# V1_4.net
KiCad netlist of a schematic drawn in Altium Designer
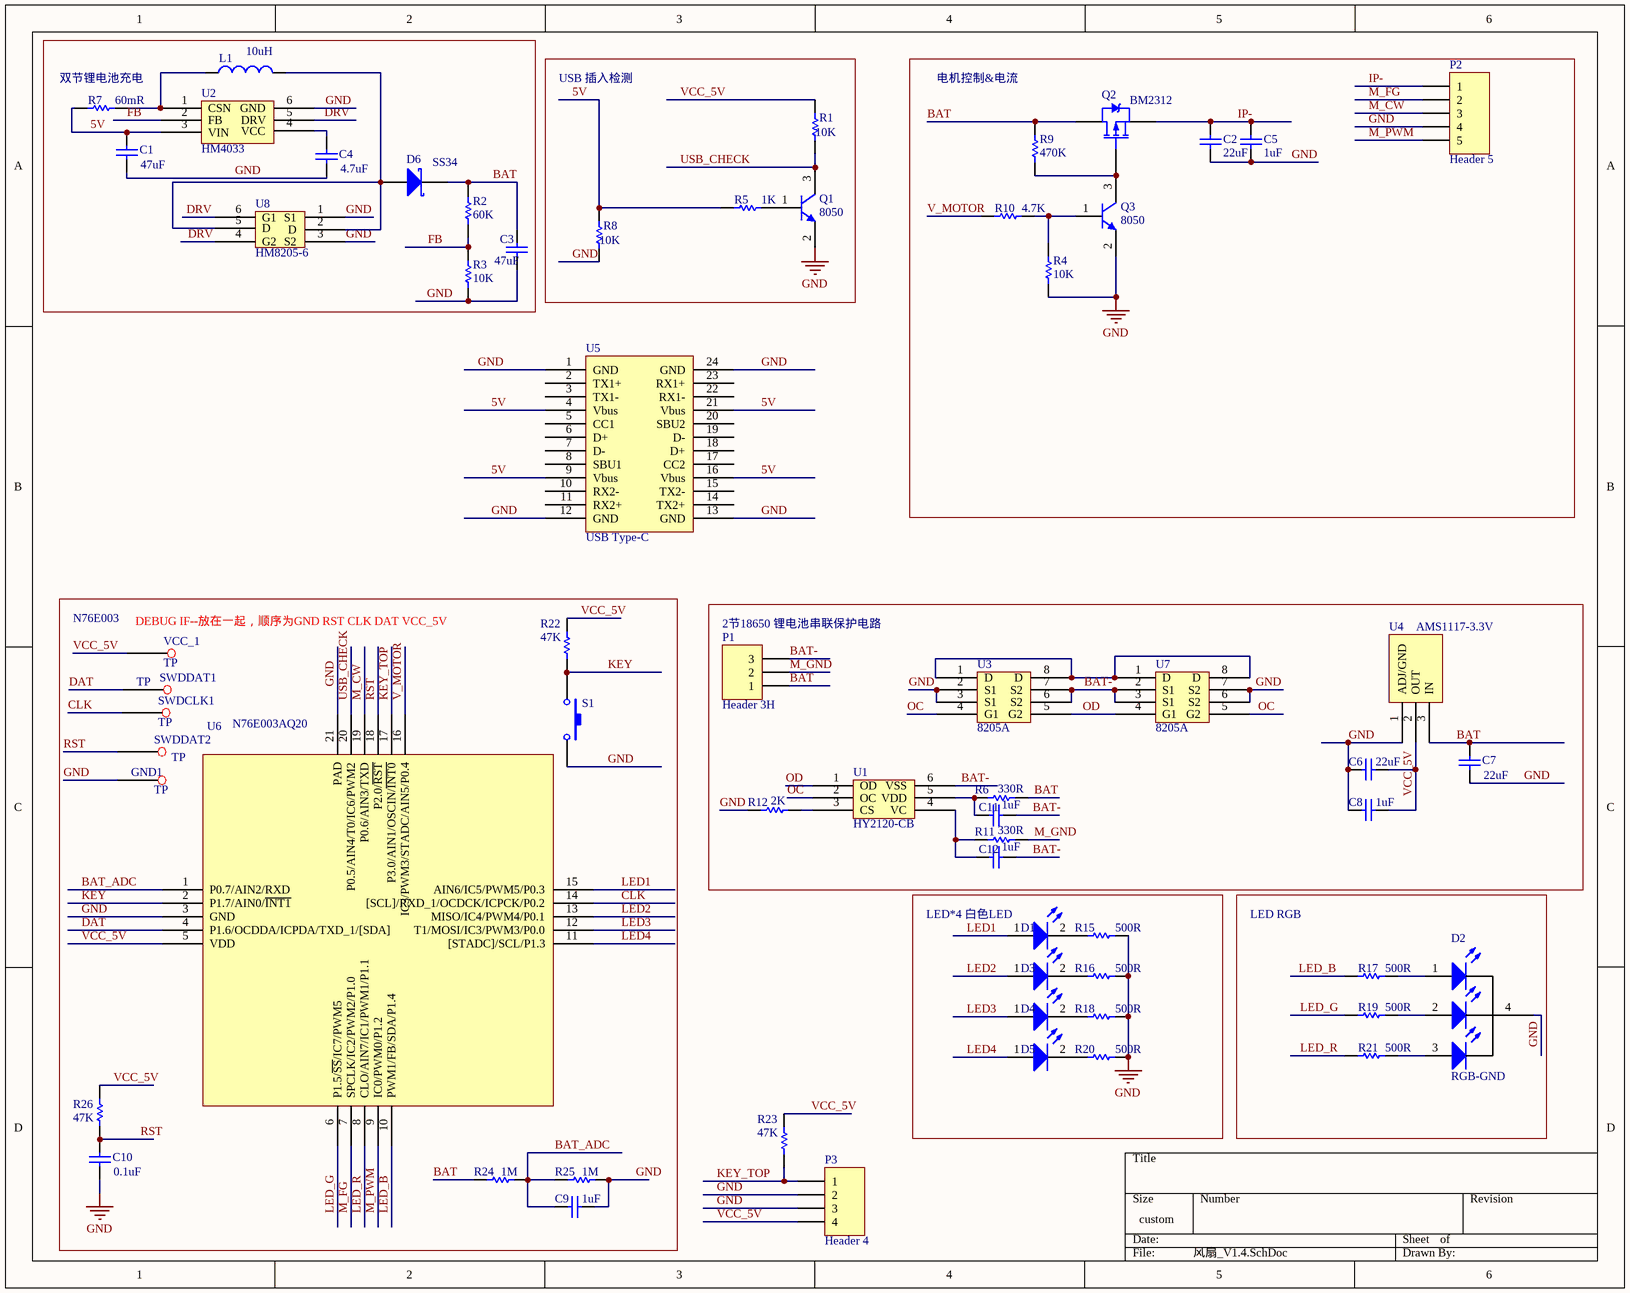
[diagram p0: 风扇_V1.4.SchDoc]

(export (version "E")
  (design (tool "Eeschema 10.0.6"))
  (components
    (comp (ref "C1")
      (value "47uF")
      (footprint "C-0603")
      (description "Capacitor")
      (fields (field (name "PUBLISHER") "Altium Limited"))
      (libsource (lib "Miscellaneous Devices") (part "Cap"))
    )
    (comp (ref "C2")
      (value "22uF")
      (footprint "C-0603")
      (description "Capacitor")
      (fields (field (name "PUBLISHER") "Altium Limited"))
      (libsource (lib "Miscellaneous Devices") (part "Cap"))
    )
    (comp (ref "C3")
      (value "47uF")
      (footprint "C-0603")
      (description "Capacitor")
      (fields (field (name "PUBLISHER") "Altium Limited"))
      (libsource (lib "Miscellaneous Devices") (part "Cap"))
    )
    (comp (ref "C4")
      (value "4.7uF")
      (footprint "C-0402")
      (description "Capacitor")
      (fields (field (name "PUBLISHER") "Altium Limited"))
      (libsource (lib "Miscellaneous Devices") (part "Cap"))
    )
    (comp (ref "C5")
      (value "1uF")
      (footprint "C-0402")
      (description "Capacitor")
      (fields (field (name "PUBLISHER") "Altium Limited"))
      (libsource (lib "Miscellaneous Devices") (part "Cap"))
    )
    (comp (ref "C6")
      (value "22uF")
      (footprint "C-0603")
      (description "Capacitor")
      (fields (field (name "PUBLISHER") "Altium Limited"))
      (libsource (lib "Miscellaneous Devices") (part "Cap"))
    )
    (comp (ref "C7")
      (value "22uF")
      (footprint "C-0603")
      (description "Capacitor")
      (fields (field (name "PUBLISHER") "Altium Limited"))
      (libsource (lib "Miscellaneous Devices") (part "Cap"))
    )
    (comp (ref "C8")
      (value "1uF")
      (footprint "C-0402")
      (description "Capacitor")
      (fields (field (name "PUBLISHER") "Altium Limited"))
      (libsource (lib "Miscellaneous Devices") (part "Cap"))
    )
    (comp (ref "C9")
      (value "1uF")
      (footprint "C-0402")
      (description "Capacitor")
      (fields (field (name "PUBLISHER") "Altium Limited"))
      (libsource (lib "Miscellaneous Devices") (part "Cap"))
    )
    (comp (ref "C10")
      (value "0.1uF")
      (footprint "C-0402")
      (description "Capacitor")
      (fields (field (name "PUBLISHER") "Altium Limited"))
      (libsource (lib "Miscellaneous Devices") (part "Cap"))
    )
    (comp (ref "C11")
      (value "1uF")
      (footprint "C-0402")
      (description "Capacitor")
      (fields (field (name "PUBLISHER") "Altium Limited"))
      (libsource (lib "Miscellaneous Devices") (part "Cap"))
    )
    (comp (ref "C12")
      (value "1uF")
      (footprint "C-0402")
      (description "Capacitor")
      (fields (field (name "PUBLISHER") "Altium Limited"))
      (libsource (lib "Miscellaneous Devices") (part "Cap"))
    )
    (comp (ref "D1")
      (value "LED0")
      (footprint "LED-0603")
      (description "Typical INFRARED GaAs LED")
      (fields (field (name "PUBLISHER") "Altium Limited"))
      (libsource (lib "Miscellaneous Devices") (part "LED0"))
    )
    (comp (ref "D2")
      (value "RGB-GND")
      (footprint "0603*2-LED")
      (libsource (lib "Others_IC_SCH_LIB") (part "RGB-GND"))
    )
    (comp (ref "D3")
      (value "LED0")
      (footprint "LED-0603")
      (description "Typical INFRARED GaAs LED")
      (fields (field (name "PUBLISHER") "Altium Limited"))
      (libsource (lib "Miscellaneous Devices") (part "LED0"))
    )
    (comp (ref "D4")
      (value "LED0")
      (footprint "LED-0603")
      (description "Typical INFRARED GaAs LED")
      (fields (field (name "PUBLISHER") "Altium Limited"))
      (libsource (lib "Miscellaneous Devices") (part "LED0"))
    )
    (comp (ref "D5")
      (value "LED0")
      (footprint "LED-0603")
      (description "Typical INFRARED GaAs LED")
      (fields (field (name "PUBLISHER") "Altium Limited"))
      (libsource (lib "Miscellaneous Devices") (part "LED0"))
    )
    (comp (ref "D6")
      (value "SS34")
      (footprint "HM4033 V1.0:DSMD")
      (description "Schottky Rectifier")
      (fields (field (name "PUBLISHER") "Altium Limited"))
      (libsource (lib "Miscellaneous Devices") (part "Diode 10TQ035"))
    )
    (comp (ref "GND1") (value "TP") (footprint "TP-1.5") (libsource (lib "Others_IC_SCH_LIB") (part "TP")))
    (comp (ref "L1")
      (value "10uH")
      (footprint "L-SMD")
      (description "Inductor")
      (fields (field (name "PUBLISHER") "Altium Limited"))
      (libsource (lib "Miscellaneous Devices") (part "Inductor"))
    )
    (comp (ref "P1")
      (value "Header 3H")
      (footprint "HED1X3")
      (description "Header, 3-Pin, Right Angle")
      (fields (field (name "PUBLISHER") "Altium Limited"))
      (libsource (lib "Miscellaneous Connectors") (part "Header 3H"))
    )
    (comp (ref "P2")
      (value "Header 5")
      (footprint "HDR1X5")
      (description "Header, 5-Pin")
      (fields (field (name "PUBLISHER") "Altium Limited"))
      (libsource (lib "Miscellaneous Connectors") (part "Header 5"))
    )
    (comp (ref "P3")
      (value "Header 4")
      (footprint "HDR1X4")
      (description "Header, 4-Pin")
      (fields (field (name "PUBLISHER") "Altium Limited"))
      (libsource (lib "Miscellaneous Connectors") (part "Header 4"))
    )
    (comp (ref "Q1")
      (value "8050")
      (footprint "SOT-23")
      (description "NPN Bipolar Transistor")
      (fields (field (name "PUBLISHER") "Altium Limited"))
      (libsource (lib "Miscellaneous Devices") (part "NPN"))
    )
    (comp (ref "Q2")
      (value "BM2312")
      (footprint "SOT-23")
      (description "P-Channel Power MOSFET")
      (fields (field (name "PUBLISHER") "Altium Limited"))
      (libsource (lib "Miscellaneous Devices") (part "PMOS-2"))
    )
    (comp (ref "Q3")
      (value "8050")
      (footprint "SOT-23")
      (description "NPN Bipolar Transistor")
      (fields (field (name "PUBLISHER") "Altium Limited"))
      (libsource (lib "Miscellaneous Devices") (part "NPN"))
    )
    (comp (ref "R1")
      (value "10K")
      (footprint "R-0402")
      (description "Resistor")
      (fields (field (name "PUBLISHER") "Altium Limited"))
      (libsource (lib "Miscellaneous Devices") (part "Res1"))
    )
    (comp (ref "R2")
      (value "60K")
      (footprint "R-0402")
      (description "Resistor")
      (fields (field (name "PUBLISHER") "Altium Limited"))
      (libsource (lib "Miscellaneous Devices") (part "Res1"))
    )
    (comp (ref "R3")
      (value "10K")
      (footprint "R-0402")
      (description "Resistor")
      (fields (field (name "PUBLISHER") "Altium Limited"))
      (libsource (lib "Miscellaneous Devices") (part "Res1"))
    )
    (comp (ref "R4")
      (value "10K")
      (footprint "R-0402")
      (description "Resistor")
      (fields (field (name "PUBLISHER") "Altium Limited"))
      (libsource (lib "Miscellaneous Devices") (part "Res1"))
    )
    (comp (ref "R5")
      (value "1K")
      (footprint "R-0402")
      (description "Resistor")
      (fields (field (name "PUBLISHER") "Altium Limited"))
      (libsource (lib "Miscellaneous Devices") (part "Res1"))
    )
    (comp (ref "R6")
      (value "330R")
      (footprint "R-0402")
      (description "Resistor")
      (fields (field (name "PUBLISHER") "Altium Limited"))
      (libsource (lib "Miscellaneous Devices") (part "Res1"))
    )
    (comp (ref "R7")
      (value "60mR")
      (footprint "R-0402")
      (description "Resistor")
      (fields (field (name "PUBLISHER") "Altium Limited"))
      (libsource (lib "Miscellaneous Devices") (part "Res1"))
    )
    (comp (ref "R8")
      (value "10K")
      (footprint "R-0402")
      (description "Resistor")
      (fields (field (name "PUBLISHER") "Altium Limited"))
      (libsource (lib "Miscellaneous Devices") (part "Res1"))
    )
    (comp (ref "R9")
      (value "470K")
      (footprint "R-0402")
      (description "Resistor")
      (fields (field (name "PUBLISHER") "Altium Limited"))
      (libsource (lib "Miscellaneous Devices") (part "Res1"))
    )
    (comp (ref "R10")
      (value "4.7K")
      (footprint "R-0402")
      (description "Resistor")
      (fields (field (name "PUBLISHER") "Altium Limited"))
      (libsource (lib "Miscellaneous Devices") (part "Res1"))
    )
    (comp (ref "R11")
      (value "330R")
      (footprint "R-0402")
      (description "Resistor")
      (fields (field (name "PUBLISHER") "Altium Limited"))
      (libsource (lib "Miscellaneous Devices") (part "Res1"))
    )
    (comp (ref "R12")
      (value "2K")
      (footprint "R-0402")
      (description "Resistor")
      (fields (field (name "PUBLISHER") "Altium Limited"))
      (libsource (lib "Miscellaneous Devices") (part "Res1"))
    )
    (comp (ref "R15")
      (value "500R")
      (footprint "R-0402")
      (description "Resistor")
      (fields (field (name "PUBLISHER") "Altium Limited"))
      (libsource (lib "Miscellaneous Devices") (part "Res1"))
    )
    (comp (ref "R16")
      (value "500R")
      (footprint "R-0402")
      (description "Resistor")
      (fields (field (name "PUBLISHER") "Altium Limited"))
      (libsource (lib "Miscellaneous Devices") (part "Res1"))
    )
    (comp (ref "R17")
      (value "500R")
      (footprint "R-0402")
      (description "Resistor")
      (fields (field (name "PUBLISHER") "Altium Limited"))
      (libsource (lib "Miscellaneous Devices") (part "Res1"))
    )
    (comp (ref "R18")
      (value "500R")
      (footprint "R-0402")
      (description "Resistor")
      (fields (field (name "PUBLISHER") "Altium Limited"))
      (libsource (lib "Miscellaneous Devices") (part "Res1"))
    )
    (comp (ref "R19")
      (value "500R")
      (footprint "R-0402")
      (description "Resistor")
      (fields (field (name "PUBLISHER") "Altium Limited"))
      (libsource (lib "Miscellaneous Devices") (part "Res1"))
    )
    (comp (ref "R20")
      (value "500R")
      (footprint "R-0402")
      (description "Resistor")
      (fields (field (name "PUBLISHER") "Altium Limited"))
      (libsource (lib "Miscellaneous Devices") (part "Res1"))
    )
    (comp (ref "R21")
      (value "500R")
      (footprint "R-0402")
      (description "Resistor")
      (fields (field (name "PUBLISHER") "Altium Limited"))
      (libsource (lib "Miscellaneous Devices") (part "Res1"))
    )
    (comp (ref "R22")
      (value "47K")
      (footprint "R-0402")
      (description "Resistor")
      (fields (field (name "PUBLISHER") "Altium Limited"))
      (libsource (lib "Miscellaneous Devices") (part "Res1"))
    )
    (comp (ref "R23")
      (value "47K")
      (footprint "R-0402")
      (description "Resistor")
      (fields (field (name "PUBLISHER") "Altium Limited"))
      (libsource (lib "Miscellaneous Devices") (part "Res1"))
    )
    (comp (ref "R24")
      (value "1M")
      (footprint "R-0402")
      (description "Resistor")
      (fields (field (name "PUBLISHER") "Altium Limited"))
      (libsource (lib "Miscellaneous Devices") (part "Res1"))
    )
    (comp (ref "R25")
      (value "1M")
      (footprint "R-0402")
      (description "Resistor")
      (fields (field (name "PUBLISHER") "Altium Limited"))
      (libsource (lib "Miscellaneous Devices") (part "Res1"))
    )
    (comp (ref "R26")
      (value "47K")
      (footprint "R-0402")
      (description "Resistor")
      (fields (field (name "PUBLISHER") "Altium Limited"))
      (libsource (lib "Miscellaneous Devices") (part "Res1"))
    )
    (comp (ref "S1")
      (value "SW-PB")
      (footprint "SW-6*6*4.3")
      (description "Switch")
      (fields (field (name "PUBLISHER") "Altium Limited"))
      (libsource (lib "Miscellaneous Devices") (part "SW-PB"))
    )
    (comp (ref "SWDCLK1") (value "TP") (footprint "TP-1.5") (libsource (lib "Others_IC_SCH_LIB") (part "TP")))
    (comp (ref "SWDDAT1") (value "TP") (footprint "TP-1.5") (libsource (lib "Others_IC_SCH_LIB") (part "TP")))
    (comp (ref "SWDDAT2") (value "TP") (footprint "TP-1.5") (libsource (lib "Others_IC_SCH_LIB") (part "TP")))
    (comp (ref "U1")
      (value "HY2120-CB")
      (footprint "SOT-23-6L")
      (libsource (lib "Others_IC_SCH_LIB") (part "HY2120"))
    )
    (comp (ref "U2")
      (value "HM4033")
      (footprint "SOT-23-6L")
      (libsource (lib "Others_IC_SCH_LIB") (part "HM4033"))
    )
    (comp (ref "U3")
      (value "8205A")
      (footprint "TSSOP8")
      (libsource (lib "Others_IC_SCH_LIB") (part "8205A"))
    )
    (comp (ref "U4")
      (value "AMS1117-3.3V")
      (footprint "SOT-223")
      (libsource (lib "Others_IC_SCH_LIB") (part "AMS1117"))
    )
    (comp (ref "U5")
      (value "USB Type-C")
      (footprint "USB-type C")
      (libsource (lib "Others_IC_SCH_LIB") (part "USB Type-C"))
    )
    (comp (ref "U6")
      (value "N76E003AQ20")
      (footprint "QFN-20 0.4mm")
      (libsource (lib "Others_IC_SCH_LIB") (part "N76E003AQ20"))
    )
    (comp (ref "U7")
      (value "8205A")
      (footprint "TSSOP8")
      (libsource (lib "Others_IC_SCH_LIB") (part "8205A"))
    )
    (comp (ref "U8")
      (value "HM8205-6")
      (footprint "SOT-23-6L")
      (libsource (lib "Others_IC_SCH_LIB") (part "HM8205-6"))
    )
    (comp (ref "VCC_1") (value "TP") (footprint "TP-1.5") (libsource (lib "Others_IC_SCH_LIB") (part "TP")))
  )
  (nets
    (net (code "1") (name "/5V") (class "Default")
      (node (ref "C1") (pin "1") (pinfunction "1_1") (pintype "passive"))
      (node (ref "R5") (pin "1") (pinfunction "1_1") (pintype "passive"))
      (node (ref "R7") (pin "2") (pinfunction "2_2") (pintype "passive"))
      (node (ref "R8") (pin "1") (pinfunction "1_1") (pintype "passive"))
      (node (ref "U2") (pin "3") (pinfunction "VIN_3") (pintype "passive"))
      (node (ref "U5") (pin "16") (pinfunction "Vbus_16") (pintype "passive"))
      (node (ref "U5") (pin "21") (pinfunction "Vbus_21") (pintype "passive"))
      (node (ref "U5") (pin "4") (pinfunction "Vbus_4") (pintype "passive"))
      (node (ref "U5") (pin "9") (pinfunction "Vbus_9") (pintype "passive"))
    )
    (net (code "2") (name "/BAT") (class "Default")
      (node (ref "C3") (pin "2") (pinfunction "2_2") (pintype "passive"))
      (node (ref "C7") (pin "2") (pinfunction "2_2") (pintype "passive"))
      (node (ref "D6") (pin "1") (pinfunction "K_1") (pintype "passive"))
      (node (ref "P1") (pin "1") (pinfunction "1_1") (pintype "passive"))
      (node (ref "Q2") (pin "2") (pinfunction "D_2") (pintype "passive"))
      (node (ref "R2") (pin "1") (pinfunction "1_1") (pintype "passive"))
      (node (ref "R24") (pin "1") (pinfunction "1_1") (pintype "passive"))
      (node (ref "R6") (pin "2") (pinfunction "2_2") (pintype "passive"))
      (node (ref "R9") (pin "2") (pinfunction "2_2") (pintype "passive"))
      (node (ref "U4") (pin "3") (pinfunction "IN_3") (pintype "passive"))
    )
    (net (code "3") (name "/BAT-") (class "Default")
      (node (ref "C11") (pin "1") (pinfunction "1_1") (pintype "passive"))
      (node (ref "C12") (pin "1") (pinfunction "1_1") (pintype "passive"))
      (node (ref "P1") (pin "3") (pinfunction "3_3") (pintype "passive"))
      (node (ref "U1") (pin "6") (pinfunction "VSS_6") (pintype "passive"))
      (node (ref "U3") (pin "6") (pinfunction "S2_6") (pintype "passive"))
      (node (ref "U3") (pin "7") (pinfunction "S2_7") (pintype "passive"))
      (node (ref "U7") (pin "2") (pinfunction "S1_2") (pintype "passive"))
      (node (ref "U7") (pin "3") (pinfunction "S1_3") (pintype "passive"))
    )
    (net (code "4") (name "/BAT_ADC") (class "Default")
      (node (ref "C9") (pin "2") (pinfunction "2_2") (pintype "passive"))
      (node (ref "R24") (pin "2") (pinfunction "2_2") (pintype "passive"))
      (node (ref "R25") (pin "1") (pinfunction "1_1") (pintype "passive"))
      (node (ref "U6") (pin "1") (pinfunction "P0.7/AIN2/RXD_1") (pintype "passive"))
    )
    (net (code "5") (name "/CLK") (class "Default")
      (node (ref "SWDCLK1") (pin "1") (pinfunction "1_1") (pintype "passive"))
      (node (ref "U6") (pin "14") (pinfunction "[SCL]/RXD_1/OCDCK/ICPCK/P0.2_14") (pintype "passive"))
    )
    (net (code "6") (name "/DAT") (class "Default")
      (node (ref "SWDDAT1") (pin "1") (pinfunction "1_1") (pintype "passive"))
      (node (ref "U6") (pin "4") (pinfunction "P1.6/OCDDA/ICPDA/TXD_1/[SDA]_4") (pintype "passive"))
    )
    (net (code "7") (name "/DRV") (class "Default")
      (node (ref "U2") (pin "5") (pinfunction "DRV_5") (pintype "passive"))
      (node (ref "U8") (pin "4") (pinfunction "G2_4") (pintype "passive"))
      (node (ref "U8") (pin "6") (pinfunction "G1_6") (pintype "passive"))
    )
    (net (code "8") (name "/FB") (class "Default")
      (node (ref "R2") (pin "2") (pinfunction "2_2") (pintype "passive"))
      (node (ref "R3") (pin "1") (pinfunction "1_1") (pintype "passive"))
      (node (ref "U2") (pin "2") (pinfunction "FB_2") (pintype "passive"))
    )
    (net (code "9") (name "/IP-") (class "Default")
      (node (ref "C2") (pin "2") (pinfunction "2_2") (pintype "passive"))
      (node (ref "C5") (pin "2") (pinfunction "2_2") (pintype "passive"))
      (node (ref "P2") (pin "1") (pinfunction "1_1") (pintype "passive"))
      (node (ref "Q2") (pin "3") (pinfunction "S_3") (pintype "passive"))
    )
    (net (code "10") (name "/KEY") (class "Default")
      (node (ref "R22") (pin "1") (pinfunction "1_1") (pintype "passive"))
      (node (ref "S1") (pin "1") (pinfunction "1_1") (pintype "passive"))
      (node (ref "U6") (pin "2") (pinfunction "P1.7/AIN0/~{INT1}_2") (pintype "passive"))
    )
    (net (code "11") (name "/KEY_TOP") (class "Default")
      (node (ref "P3") (pin "1") (pinfunction "1_1") (pintype "passive"))
      (node (ref "R23") (pin "1") (pinfunction "1_1") (pintype "passive"))
      (node (ref "U6") (pin "17") (pinfunction "P3.0/AIN1/OSCIN/~{INT0}_17") (pintype "passive"))
    )
    (net (code "12") (name "/LED1") (class "Default")
      (node (ref "D1") (pin "1") (pinfunction "A_1") (pintype "passive"))
      (node (ref "U6") (pin "15") (pinfunction "AIN6/IC5/PWM5/P0.3_15") (pintype "passive"))
    )
    (net (code "13") (name "/LED2") (class "Default")
      (node (ref "D3") (pin "1") (pinfunction "A_1") (pintype "passive"))
      (node (ref "U6") (pin "13") (pinfunction "MISO/IC4/PWM4/P0.1_13") (pintype "passive"))
    )
    (net (code "14") (name "/LED3") (class "Default")
      (node (ref "D4") (pin "1") (pinfunction "A_1") (pintype "passive"))
      (node (ref "U6") (pin "12") (pinfunction "T1/MOSI/IC3/PWM3/P0.0_12") (pintype "passive"))
    )
    (net (code "15") (name "/LED4") (class "Default")
      (node (ref "D5") (pin "1") (pinfunction "A_1") (pintype "passive"))
      (node (ref "U6") (pin "11") (pinfunction "[STADC]/SCL/P1.3_11") (pintype "passive"))
    )
    (net (code "16") (name "/LED_B") (class "Default")
      (node (ref "R17") (pin "1") (pinfunction "1_1") (pintype "passive"))
      (node (ref "U6") (pin "10") (pinfunction "PWM1/FB/SDA/P1.4_10") (pintype "passive"))
    )
    (net (code "17") (name "/LED_G") (class "Default")
      (node (ref "R19") (pin "1") (pinfunction "1_1") (pintype "passive"))
      (node (ref "U6") (pin "6") (pinfunction "P1.5/~{SS}/IC7/PWM5_6") (pintype "passive"))
    )
    (net (code "18") (name "/LED_R") (class "Default")
      (node (ref "R21") (pin "1") (pinfunction "1_1") (pintype "passive"))
      (node (ref "U6") (pin "8") (pinfunction "CLO/AIN7/IC1/PWM1/P1.1_8") (pintype "passive"))
    )
    (net (code "19") (name "/M_CW") (class "Default")
      (node (ref "P2") (pin "3") (pinfunction "3_3") (pintype "passive"))
      (node (ref "U6") (pin "19") (pinfunction "P0.6/AIN3/TXD_19") (pintype "passive"))
    )
    (net (code "20") (name "/M_FG") (class "Default")
      (node (ref "P2") (pin "2") (pinfunction "2_2") (pintype "passive"))
      (node (ref "U6") (pin "7") (pinfunction "SPCLK/IC2/PWM2/P1.0_7") (pintype "passive"))
    )
    (net (code "21") (name "/M_GND") (class "Default")
      (node (ref "P1") (pin "2") (pinfunction "2_2") (pintype "passive"))
      (node (ref "R11") (pin "2") (pinfunction "2_2") (pintype "passive"))
    )
    (net (code "22") (name "/M_PWM") (class "Default")
      (node (ref "P2") (pin "5") (pinfunction "5_5") (pintype "passive"))
      (node (ref "U6") (pin "9") (pinfunction "IC0/PWM0/P1.2_9") (pintype "passive"))
    )
    (net (code "23") (name "/OC") (class "Default")
      (node (ref "U1") (pin "2") (pinfunction "OC_2") (pintype "passive"))
      (node (ref "U3") (pin "4") (pinfunction "G1_4") (pintype "passive"))
      (node (ref "U7") (pin "5") (pinfunction "G2_5") (pintype "passive"))
    )
    (net (code "24") (name "/OD") (class "Default")
      (node (ref "U1") (pin "1") (pinfunction "OD_1") (pintype "passive"))
      (node (ref "U3") (pin "5") (pinfunction "G2_5") (pintype "passive"))
      (node (ref "U7") (pin "4") (pinfunction "G1_4") (pintype "passive"))
    )
    (net (code "25") (name "/RST") (class "Default")
      (node (ref "C10") (pin "2") (pinfunction "2_2") (pintype "passive"))
      (node (ref "R26") (pin "1") (pinfunction "1_1") (pintype "passive"))
      (node (ref "SWDDAT2") (pin "1") (pinfunction "1_1") (pintype "passive"))
      (node (ref "U6") (pin "18") (pinfunction "P2.0/~{RST}_18") (pintype "passive"))
    )
    (net (code "26") (name "/USB_CHECK") (class "Default")
      (node (ref "Q1") (pin "3") (pinfunction "C_3") (pintype "passive"))
      (node (ref "R1") (pin "1") (pinfunction "1_1") (pintype "passive"))
      (node (ref "U6") (pin "20") (pinfunction "P0.5/AIN4/T0/IC6/PWM2_20") (pintype "passive"))
    )
    (net (code "27") (name "/VCC_5V") (class "Default")
      (node (ref "C6") (pin "2") (pinfunction "2_2") (pintype "passive"))
      (node (ref "C8") (pin "2") (pinfunction "2_2") (pintype "passive"))
      (node (ref "P3") (pin "4") (pinfunction "4_4") (pintype "passive"))
      (node (ref "R1") (pin "2") (pinfunction "2_2") (pintype "passive"))
      (node (ref "R22") (pin "2") (pinfunction "2_2") (pintype "passive"))
      (node (ref "R23") (pin "2") (pinfunction "2_2") (pintype "passive"))
      (node (ref "R26") (pin "2") (pinfunction "2_2") (pintype "passive"))
      (node (ref "U4") (pin "2") (pinfunction "OUT_2") (pintype "passive"))
      (node (ref "U6") (pin "5") (pinfunction "VDD_5") (pintype "passive"))
      (node (ref "VCC_1") (pin "1") (pinfunction "1_1") (pintype "passive"))
    )
    (net (code "28") (name "/V_MOTOR") (class "Default")
      (node (ref "R10") (pin "1") (pinfunction "1_1") (pintype "passive"))
      (node (ref "U6") (pin "16") (pinfunction "IC3/PWM3/STADC/AIN5/P0.4_16") (pintype "passive"))
    )
    (net (code "29") (name "GND") (class "Default")
      (node (ref "C1") (pin "2") (pinfunction "2_2") (pintype "passive"))
      (node (ref "C10") (pin "1") (pinfunction "1_1") (pintype "passive"))
      (node (ref "C2") (pin "1") (pinfunction "1_1") (pintype "passive"))
      (node (ref "C3") (pin "1") (pinfunction "1_1") (pintype "passive"))
      (node (ref "C4") (pin "2") (pinfunction "2_2") (pintype "passive"))
      (node (ref "C5") (pin "1") (pinfunction "1_1") (pintype "passive"))
      (node (ref "C6") (pin "1") (pinfunction "1_1") (pintype "passive"))
      (node (ref "C7") (pin "1") (pinfunction "1_1") (pintype "passive"))
      (node (ref "C8") (pin "1") (pinfunction "1_1") (pintype "passive"))
      (node (ref "C9") (pin "1") (pinfunction "1_1") (pintype "passive"))
      (node (ref "D2") (pin "4") (pinfunction "4_4") (pintype "passive"))
      (node (ref "GND1") (pin "1") (pinfunction "1_1") (pintype "passive"))
      (node (ref "P2") (pin "4") (pinfunction "4_4") (pintype "passive"))
      (node (ref "P3") (pin "2") (pinfunction "2_2") (pintype "passive"))
      (node (ref "P3") (pin "3") (pinfunction "3_3") (pintype "passive"))
      (node (ref "Q1") (pin "2") (pinfunction "E_2") (pintype "passive"))
      (node (ref "Q3") (pin "2") (pinfunction "E_2") (pintype "passive"))
      (node (ref "R12") (pin "1") (pinfunction "1_1") (pintype "passive"))
      (node (ref "R15") (pin "2") (pinfunction "2_2") (pintype "passive"))
      (node (ref "R16") (pin "2") (pinfunction "2_2") (pintype "passive"))
      (node (ref "R18") (pin "2") (pinfunction "2_2") (pintype "passive"))
      (node (ref "R20") (pin "2") (pinfunction "2_2") (pintype "passive"))
      (node (ref "R25") (pin "2") (pinfunction "2_2") (pintype "passive"))
      (node (ref "R3") (pin "2") (pinfunction "2_2") (pintype "passive"))
      (node (ref "R4") (pin "1") (pinfunction "1_1") (pintype "passive"))
      (node (ref "R8") (pin "2") (pinfunction "2_2") (pintype "passive"))
      (node (ref "S1") (pin "2") (pinfunction "2_2") (pintype "passive"))
      (node (ref "U2") (pin "6") (pinfunction "GND_6") (pintype "passive"))
      (node (ref "U3") (pin "2") (pinfunction "S1_2") (pintype "passive"))
      (node (ref "U3") (pin "3") (pinfunction "S1_3") (pintype "passive"))
      (node (ref "U4") (pin "1") (pinfunction "ADJ/GND_1") (pintype "passive"))
      (node (ref "U5") (pin "1") (pinfunction "GND_1") (pintype "passive"))
      (node (ref "U5") (pin "12") (pinfunction "GND_12") (pintype "passive"))
      (node (ref "U5") (pin "13") (pinfunction "GND_13") (pintype "passive"))
      (node (ref "U5") (pin "24") (pinfunction "GND_24") (pintype "passive"))
      (node (ref "U6") (pin "21") (pinfunction "PAD_21") (pintype "passive"))
      (node (ref "U6") (pin "3") (pinfunction "GND_3") (pintype "passive"))
      (node (ref "U7") (pin "6") (pinfunction "S2_6") (pintype "passive"))
      (node (ref "U7") (pin "7") (pinfunction "S2_7") (pintype "passive"))
      (node (ref "U8") (pin "1") (pinfunction "S1_1") (pintype "passive"))
      (node (ref "U8") (pin "3") (pinfunction "S2_3") (pintype "passive"))
    )
    (net (code "30") (name "Net-(D1-K)") (class "Default")
      (node (ref "D1") (pin "2") (pinfunction "K_2") (pintype "passive"))
      (node (ref "R15") (pin "1") (pinfunction "1_1") (pintype "passive"))
    )
    (net (code "31") (name "Net-(D2-Pad1)") (class "Default")
      (node (ref "D2") (pin "1") (pinfunction "1_1") (pintype "passive"))
      (node (ref "R17") (pin "2") (pinfunction "2_2") (pintype "passive"))
    )
    (net (code "32") (name "Net-(D2-Pad2)") (class "Default")
      (node (ref "D2") (pin "2") (pinfunction "2_2") (pintype "passive"))
      (node (ref "R19") (pin "2") (pinfunction "2_2") (pintype "passive"))
    )
    (net (code "33") (name "Net-(D2-Pad3)") (class "Default")
      (node (ref "D2") (pin "3") (pinfunction "3_3") (pintype "passive"))
      (node (ref "R21") (pin "2") (pinfunction "2_2") (pintype "passive"))
    )
    (net (code "34") (name "Net-(D3-K)") (class "Default")
      (node (ref "D3") (pin "2") (pinfunction "K_2") (pintype "passive"))
      (node (ref "R16") (pin "1") (pinfunction "1_1") (pintype "passive"))
    )
    (net (code "35") (name "Net-(D4-K)") (class "Default")
      (node (ref "D4") (pin "2") (pinfunction "K_2") (pintype "passive"))
      (node (ref "R18") (pin "1") (pinfunction "1_1") (pintype "passive"))
    )
    (net (code "36") (name "Net-(D5-K)") (class "Default")
      (node (ref "D5") (pin "2") (pinfunction "K_2") (pintype "passive"))
      (node (ref "R20") (pin "1") (pinfunction "1_1") (pintype "passive"))
    )
    (net (code "37") (name "Net-(D6-A)") (class "Default")
      (node (ref "D6") (pin "3") (pinfunction "A_3") (pintype "passive"))
      (node (ref "L1") (pin "2") (pinfunction "2_2") (pintype "passive"))
      (node (ref "U8") (pin "2") (pinfunction "D_2") (pintype "passive"))
      (node (ref "U8") (pin "5") (pinfunction "D_5") (pintype "passive"))
    )
    (net (code "38") (name "Net-(Q1-B)") (class "Default")
      (node (ref "Q1") (pin "1") (pinfunction "B_1") (pintype "passive"))
      (node (ref "R5") (pin "2") (pinfunction "2_2") (pintype "passive"))
    )
    (net (code "39") (name "Net-(Q2-G)") (class "Default")
      (node (ref "Q2") (pin "1") (pinfunction "G_1") (pintype "passive"))
      (node (ref "Q3") (pin "3") (pinfunction "C_3") (pintype "passive"))
      (node (ref "R9") (pin "1") (pinfunction "1_1") (pintype "passive"))
    )
    (net (code "40") (name "Net-(Q3-B)") (class "Default")
      (node (ref "Q3") (pin "1") (pinfunction "B_1") (pintype "passive"))
      (node (ref "R10") (pin "2") (pinfunction "2_2") (pintype "passive"))
      (node (ref "R4") (pin "2") (pinfunction "2_2") (pintype "passive"))
    )
    (net (code "41") (name "Net-(U1-CS)") (class "Default")
      (node (ref "R12") (pin "2") (pinfunction "2_2") (pintype "passive"))
      (node (ref "U1") (pin "3") (pinfunction "CS_3") (pintype "passive"))
    )
    (net (code "42") (name "Net-(U1-VC)") (class "Default")
      (node (ref "C12") (pin "2") (pinfunction "2_2") (pintype "passive"))
      (node (ref "R11") (pin "1") (pinfunction "1_1") (pintype "passive"))
      (node (ref "U1") (pin "4") (pinfunction "VC_4") (pintype "passive"))
    )
    (net (code "43") (name "Net-(U1-VDD)") (class "Default")
      (node (ref "C11") (pin "2") (pinfunction "2_2") (pintype "passive"))
      (node (ref "R6") (pin "1") (pinfunction "1_1") (pintype "passive"))
      (node (ref "U1") (pin "5") (pinfunction "VDD_5") (pintype "passive"))
    )
    (net (code "44") (name "Net-(U2-CSN)") (class "Default")
      (node (ref "L1") (pin "1") (pinfunction "1_1") (pintype "passive"))
      (node (ref "R7") (pin "1") (pinfunction "1_1") (pintype "passive"))
      (node (ref "U2") (pin "1") (pinfunction "CSN_1") (pintype "passive"))
    )
    (net (code "45") (name "Net-(U2-VCC)") (class "Default")
      (node (ref "C4") (pin "1") (pinfunction "1_1") (pintype "passive"))
      (node (ref "U2") (pin "4") (pinfunction "VCC_4") (pintype "passive"))
    )
    (net (code "46") (name "Net-(U3-D-Pad1)") (class "Default")
      (node (ref "U3") (pin "1") (pinfunction "D_1") (pintype "passive"))
      (node (ref "U3") (pin "8") (pinfunction "D_8") (pintype "passive"))
      (node (ref "U7") (pin "1") (pinfunction "D_1") (pintype "passive"))
      (node (ref "U7") (pin "8") (pinfunction "D_8") (pintype "passive"))
    )
    (net (code "47") (name "unconnected-(U5-CC1-Pad5)") (class "Default")
      (node (ref "U5") (pin "5") (pinfunction "CC1_5") (pintype "passive"))
    )
    (net (code "48") (name "unconnected-(U5-CC2-Pad17)") (class "Default")
      (node (ref "U5") (pin "17") (pinfunction "CC2_17") (pintype "passive"))
    )
    (net (code "49") (name "unconnected-(U5-D+-Pad6)") (class "Default")
      (node (ref "U5") (pin "6") (pinfunction "D+_6") (pintype "passive"))
    )
    (net (code "50") (name "unconnected-(U5-D+-Pad18)") (class "Default")
      (node (ref "U5") (pin "18") (pinfunction "D+_18") (pintype "passive"))
    )
    (net (code "51") (name "unconnected-(U5-D--Pad7)") (class "Default")
      (node (ref "U5") (pin "7") (pinfunction "D-_7") (pintype "passive"))
    )
    (net (code "52") (name "unconnected-(U5-D--Pad19)") (class "Default")
      (node (ref "U5") (pin "19") (pinfunction "D-_19") (pintype "passive"))
    )
    (net (code "53") (name "unconnected-(U5-RX1+-Pad23)") (class "Default")
      (node (ref "U5") (pin "23") (pinfunction "RX1+_23") (pintype "passive"))
    )
    (net (code "54") (name "unconnected-(U5-RX1--Pad22)") (class "Default")
      (node (ref "U5") (pin "22") (pinfunction "RX1-_22") (pintype "passive"))
    )
    (net (code "55") (name "unconnected-(U5-RX2+-Pad11)") (class "Default")
      (node (ref "U5") (pin "11") (pinfunction "RX2+_11") (pintype "passive"))
    )
    (net (code "56") (name "unconnected-(U5-RX2--Pad10)") (class "Default")
      (node (ref "U5") (pin "10") (pinfunction "RX2-_10") (pintype "passive"))
    )
    (net (code "57") (name "unconnected-(U5-SBU1-Pad8)") (class "Default")
      (node (ref "U5") (pin "8") (pinfunction "SBU1_8") (pintype "passive"))
    )
    (net (code "58") (name "unconnected-(U5-SBU2-Pad20)") (class "Default")
      (node (ref "U5") (pin "20") (pinfunction "SBU2_20") (pintype "passive"))
    )
    (net (code "59") (name "unconnected-(U5-TX1+-Pad2)") (class "Default")
      (node (ref "U5") (pin "2") (pinfunction "TX1+_2") (pintype "passive"))
    )
    (net (code "60") (name "unconnected-(U5-TX1--Pad3)") (class "Default")
      (node (ref "U5") (pin "3") (pinfunction "TX1-_3") (pintype "passive"))
    )
    (net (code "61") (name "unconnected-(U5-TX2+-Pad14)") (class "Default")
      (node (ref "U5") (pin "14") (pinfunction "TX2+_14") (pintype "passive"))
    )
    (net (code "62") (name "unconnected-(U5-TX2--Pad15)") (class "Default")
      (node (ref "U5") (pin "15") (pinfunction "TX2-_15") (pintype "passive"))
    )
  )
)
